# S7CAS-PLEIADES-CARTE-MERE_Pxx_CAN.net
KiCad netlist of a schematic drawn in Altium Designer
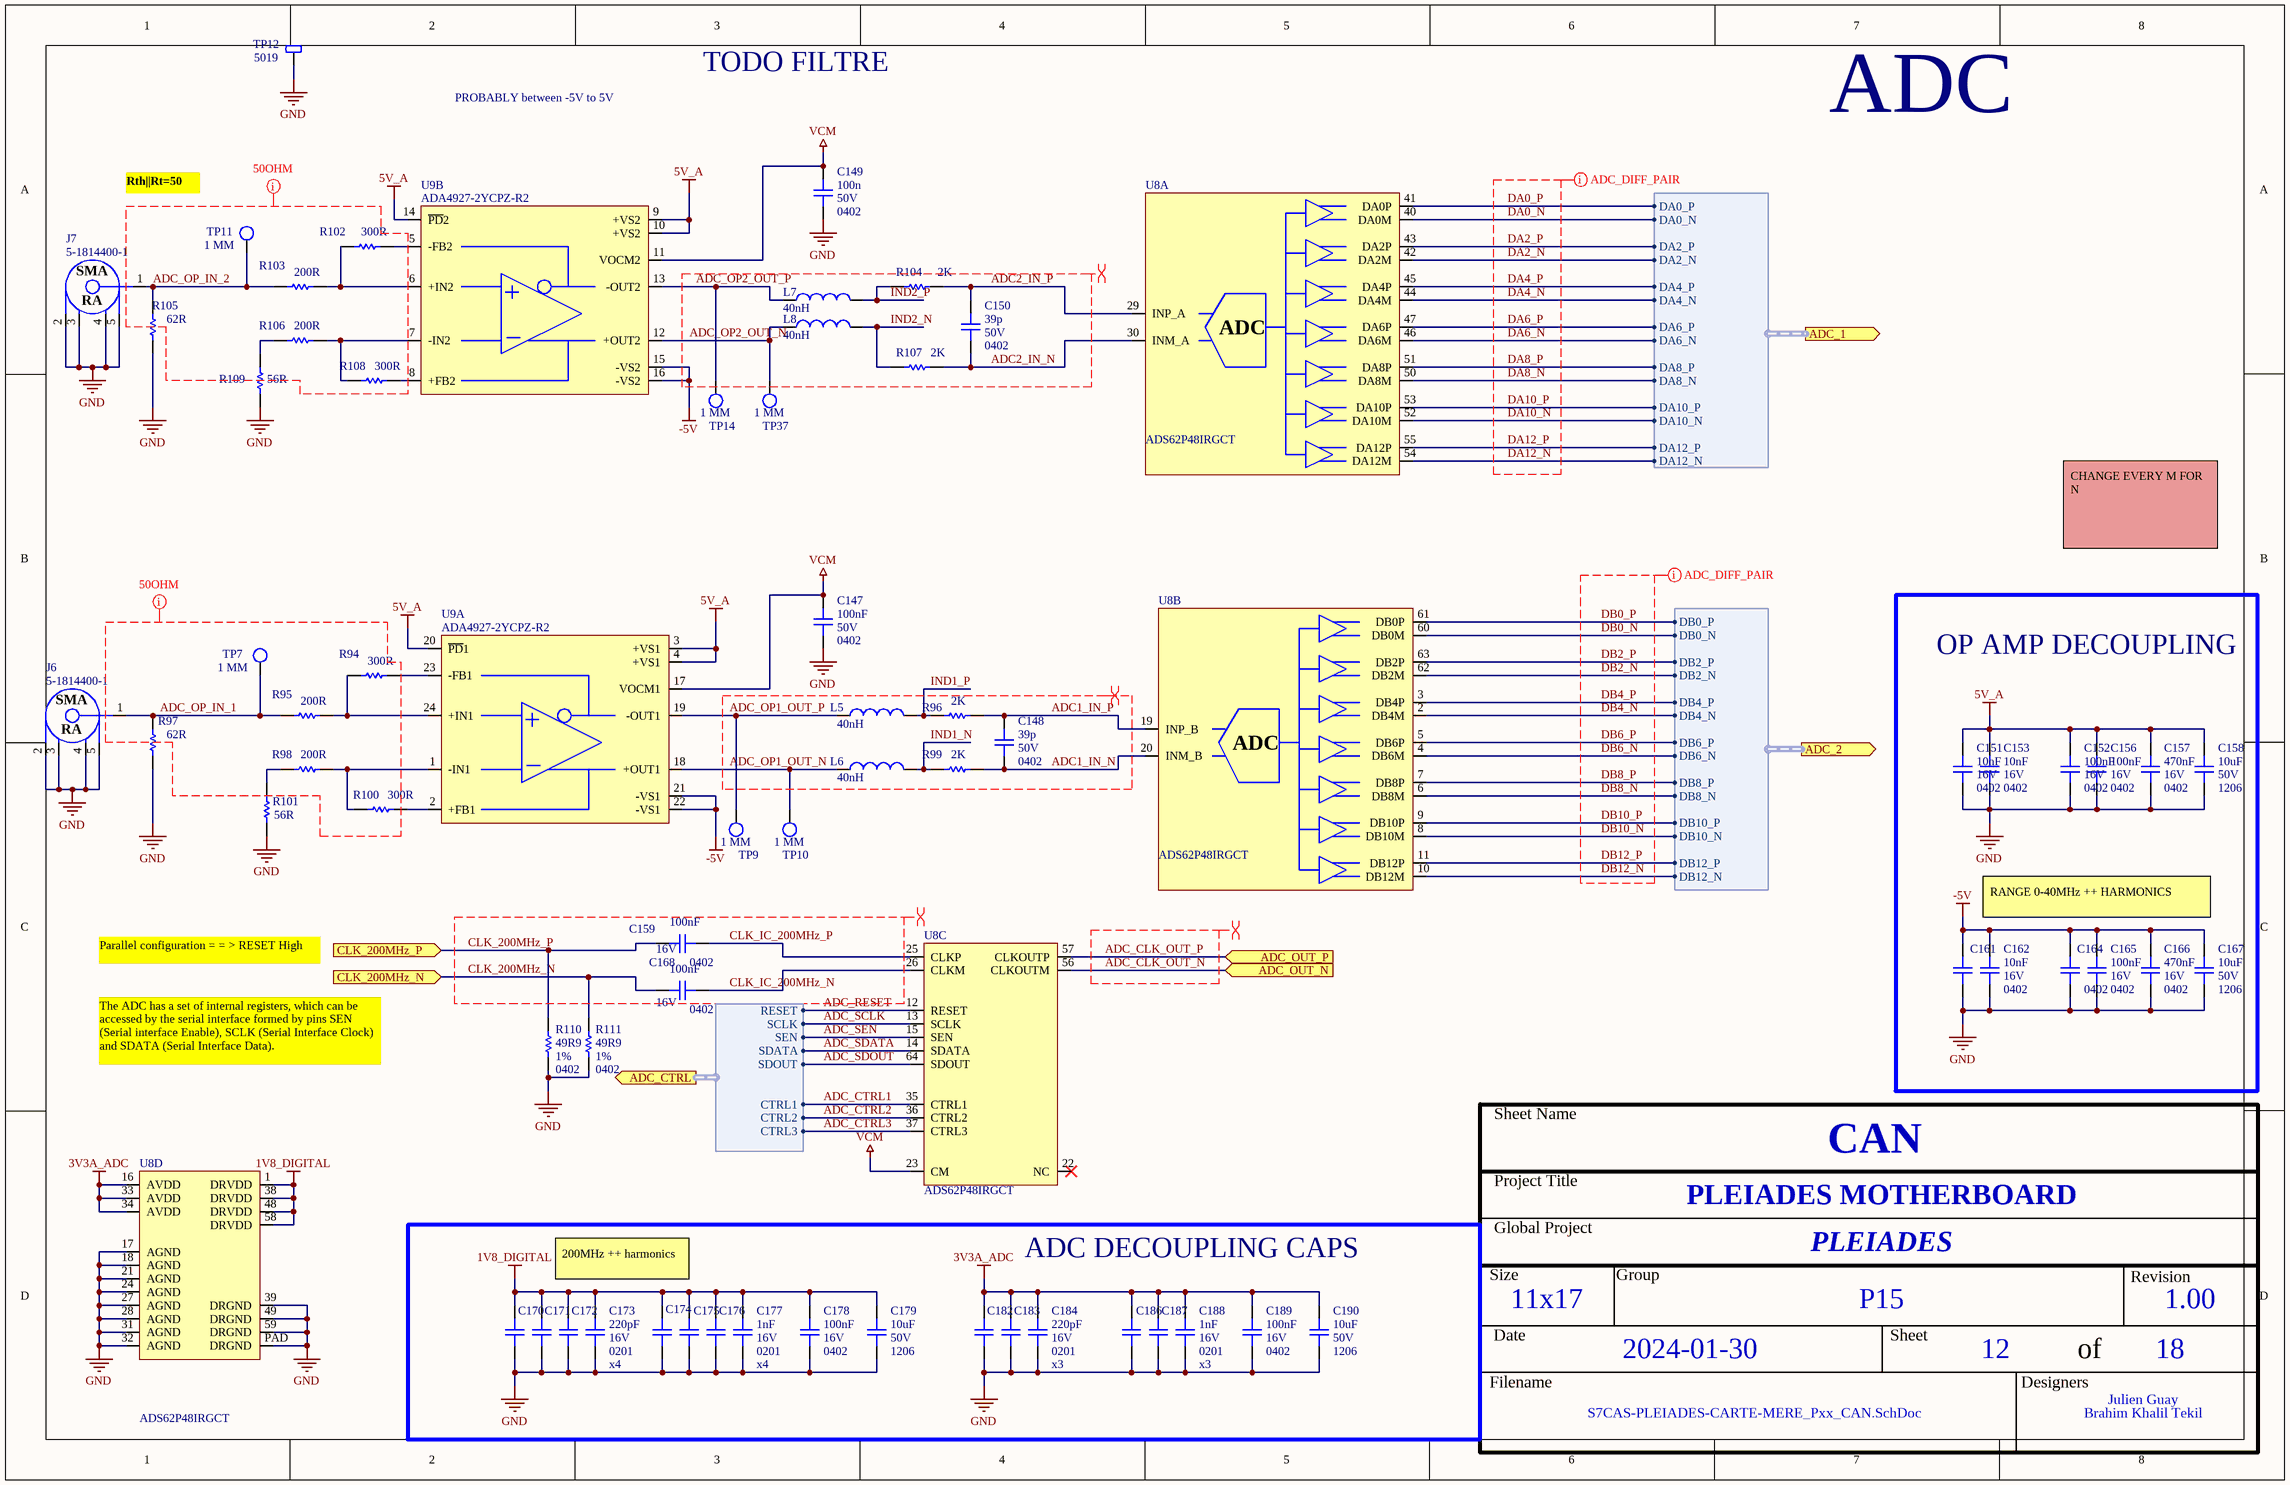
[diagram p0: S7CAS-PLEIADES-CARTE-MERE_Pxx_CAN.SchDoc]

(export (version "E")
  (design (tool "Eeschema 10.0.6"))
  (components
    (comp (ref "C147")
      (value "100nF")
      (footprint "S7CAS_LIB2023:CAP_0402")
      (description "CAP - 0402")
      (fields
        (field (name "VOLTAGE") "50V")
        (field (name "PACKAGE") "0402")
        (field (name "Comment") "0402")
        (field (name "CREATEDBY") "Jonathan Bouchard")
      )
      (libsource (lib "S7CAS_LIB2023") (part "CAP - 0603"))
    )
    (comp (ref "C148")
      (value "39p")
      (footprint "S7CAS_LIB2023:CAP_0402")
      (description "CAP - 0402")
      (fields
        (field (name "VOLTAGE") "50V")
        (field (name "PACKAGE") "0402")
        (field (name "Comment") "0402")
        (field (name "CREATEDBY") "Jonathan Bouchard")
      )
      (libsource (lib "S7CAS_LIB2023") (part "CAP - 0603"))
    )
    (comp (ref "C149")
      (value "100n")
      (footprint "S7CAS_LIB2023:CAP_0402")
      (description "CAP - 0402")
      (fields
        (field (name "VOLTAGE") "50V")
        (field (name "PACKAGE") "0402")
        (field (name "Comment") "0402")
        (field (name "CREATEDBY") "Jonathan Bouchard")
      )
      (libsource (lib "S7CAS_LIB2023") (part "CAP - 0603"))
    )
    (comp (ref "C150")
      (value "39p")
      (footprint "S7CAS_LIB2023:CAP_0402")
      (description "CAP - 0402")
      (fields
        (field (name "VOLTAGE") "50V")
        (field (name "PACKAGE") "0402")
        (field (name "Comment") "0402")
        (field (name "CREATEDBY") "Jonathan Bouchard")
      )
      (libsource (lib "S7CAS_LIB2023") (part "CAP - 0603"))
    )
    (comp (ref "C151")
      (value "10nF")
      (footprint "CAP_0402")
      (description "CAP - 0402")
      (fields
        (field (name "VOLTAGE") "16V")
        (field (name "PACKAGE") "0402")
        (field (name "CREATEDBY") "Jonathan Bouchard")
      )
      (libsource (lib "S7CAS_LIB2023") (part "CAP - 0402"))
    )
    (comp (ref "C152")
      (value "100nF")
      (footprint "S7CAS_LIB2023:CAP_0402")
      (description "CAP - 0402")
      (fields
        (field (name "VOLTAGE") "16V")
        (field (name "PACKAGE") "0402")
        (field (name "Comment") "0402")
        (field (name "CREATEDBY") "Jonathan Bouchard")
      )
      (libsource (lib "S7CAS_LIB2023") (part "CAP - 0603"))
    )
    (comp (ref "C153")
      (value "10nF")
      (footprint "CAP_0402")
      (description "CAP - 0402")
      (fields
        (field (name "VOLTAGE") "16V")
        (field (name "PACKAGE") "0402")
        (field (name "CREATEDBY") "Jonathan Bouchard")
      )
      (libsource (lib "S7CAS_LIB2023") (part "CAP - 0402"))
    )
    (comp (ref "C156")
      (value "100nF")
      (footprint "S7CAS_LIB2023:CAP_0402")
      (description "CAP - 0402")
      (fields
        (field (name "VOLTAGE") "16V")
        (field (name "PACKAGE") "0402")
        (field (name "Comment") "0402")
        (field (name "CREATEDBY") "Jonathan Bouchard")
      )
      (libsource (lib "S7CAS_LIB2023") (part "CAP - 0603"))
    )
    (comp (ref "C157")
      (value "470nF")
      (footprint "S7CAS_LIB2023:CAP_0402")
      (description "CAP - 0402")
      (fields
        (field (name "VOLTAGE") "16V")
        (field (name "PACKAGE") "0402")
        (field (name "Comment") "0402")
        (field (name "CREATEDBY") "Jonathan Bouchard")
      )
      (libsource (lib "S7CAS_LIB2023") (part "CAP - 0603"))
    )
    (comp (ref "C158")
      (value "10uF")
      (footprint "S7CAS_LIB2023:CAP_1206")
      (description "CAP - 1206")
      (fields
        (field (name "VOLTAGE") "50V")
        (field (name "PACKAGE") "1206")
        (field (name "CREATEDBY") "Jonathan Bouchard")
      )
      (libsource (lib "S7CAS_LIB2023") (part "CAP - 1206"))
    )
    (comp (ref "C159")
      (value "100nF")
      (footprint "S7CAS_LIB2023:CAP_0402")
      (description "CAP - 0402")
      (fields
        (field (name "VOLTAGE") "16V")
        (field (name "PACKAGE") "0402")
        (field (name "Comment") "0402")
        (field (name "CREATEDBY") "Jonathan Bouchard")
      )
      (libsource (lib "S7CAS_LIB2023") (part "CAP - 0603"))
    )
    (comp (ref "C161")
      (value "CAP - 0402")
      (footprint "CAP_0402")
      (fields (field (name "VOLTAGE") "16V") (field (name "CREATEDBY") "Jonathan Bouchard"))
      (libsource (lib "S7CAS_LIB2023") (part "CAP - 0402"))
    )
    (comp (ref "C162")
      (value "10nF")
      (footprint "CAP_0402")
      (description "CAP - 0402")
      (fields
        (field (name "VOLTAGE") "16V")
        (field (name "PACKAGE") "0402")
        (field (name "CREATEDBY") "Jonathan Bouchard")
      )
      (libsource (lib "S7CAS_LIB2023") (part "CAP - 0402"))
    )
    (comp (ref "C164")
      (value "0402")
      (footprint "S7CAS_LIB2023:CAP_0402")
      (description "CAP - 0402")
      (fields
        (field (name "VOLTAGE") "16V")
        (field (name "PACKAGE") "0402")
        (field (name "CREATEDBY") "Jonathan Bouchard")
      )
      (libsource (lib "S7CAS_LIB2023") (part "CAP - 0603"))
    )
    (comp (ref "C165")
      (value "100nF")
      (footprint "S7CAS_LIB2023:CAP_0402")
      (description "CAP - 0402")
      (fields
        (field (name "VOLTAGE") "16V")
        (field (name "PACKAGE") "0402")
        (field (name "Comment") "0402")
        (field (name "CREATEDBY") "Jonathan Bouchard")
      )
      (libsource (lib "S7CAS_LIB2023") (part "CAP - 0603"))
    )
    (comp (ref "C166")
      (value "470nF")
      (footprint "S7CAS_LIB2023:CAP_0402")
      (description "CAP - 0402")
      (fields
        (field (name "VOLTAGE") "16V")
        (field (name "PACKAGE") "0402")
        (field (name "Comment") "0402")
        (field (name "CREATEDBY") "Jonathan Bouchard")
      )
      (libsource (lib "S7CAS_LIB2023") (part "CAP - 0603"))
    )
    (comp (ref "C167")
      (value "10uF")
      (footprint "S7CAS_LIB2023:CAP_1206")
      (description "CAP - 1206")
      (fields
        (field (name "VOLTAGE") "50V")
        (field (name "PACKAGE") "1206")
        (field (name "CREATEDBY") "Jonathan Bouchard")
      )
      (libsource (lib "S7CAS_LIB2023") (part "CAP - 1206"))
    )
    (comp (ref "C168")
      (value "100nF")
      (footprint "S7CAS_LIB2023:CAP_0402")
      (description "CAP - 0402")
      (fields
        (field (name "VOLTAGE") "16V")
        (field (name "PACKAGE") "0402")
        (field (name "Comment") "0402")
        (field (name "CREATEDBY") "Jonathan Bouchard")
      )
      (libsource (lib "S7CAS_LIB2023") (part "CAP - 0603"))
    )
    (comp (ref "C170")
      (value "CAP - 0201")
      (footprint "CAP_0201")
      (fields (field (name "VOLTAGE") "16V") (field (name "CREATEDBY") "Jonathan Bouchard"))
      (libsource (lib "S7CAS_LIB2023") (part "CAP - 0201"))
    )
    (comp (ref "C171")
      (value "CAP - 0201")
      (footprint "CAP_0201")
      (fields (field (name "VOLTAGE") "16V") (field (name "CREATEDBY") "Jonathan Bouchard"))
      (libsource (lib "S7CAS_LIB2023") (part "CAP - 0201"))
    )
    (comp (ref "C172")
      (value "CAP - 0201")
      (footprint "CAP_0201")
      (fields (field (name "VOLTAGE") "16V") (field (name "CREATEDBY") "Jonathan Bouchard"))
      (libsource (lib "S7CAS_LIB2023") (part "CAP - 0201"))
    )
    (comp (ref "C173")
      (value "220pF")
      (footprint "CAP_0201")
      (description "CAP - 0201")
      (fields
        (field (name "VOLTAGE") "16V")
        (field (name "PACKAGE") "0201")
        (field (name "CREATEDBY") "Jonathan Bouchard")
      )
      (libsource (lib "S7CAS_LIB2023") (part "CAP - 0201"))
    )
    (comp (ref "C174")
      (value "CAP - 0201")
      (footprint "CAP_0201")
      (fields (field (name "VOLTAGE") "16V") (field (name "CREATEDBY") "Jonathan Bouchard"))
      (libsource (lib "S7CAS_LIB2023") (part "CAP - 0201"))
    )
    (comp (ref "C175")
      (value "CAP - 0201")
      (footprint "CAP_0201")
      (fields (field (name "VOLTAGE") "16V") (field (name "CREATEDBY") "Jonathan Bouchard"))
      (libsource (lib "S7CAS_LIB2023") (part "CAP - 0201"))
    )
    (comp (ref "C176")
      (value "CAP - 0201")
      (footprint "CAP_0201")
      (fields (field (name "VOLTAGE") "16V") (field (name "CREATEDBY") "Jonathan Bouchard"))
      (libsource (lib "S7CAS_LIB2023") (part "CAP - 0201"))
    )
    (comp (ref "C177")
      (value "1nF")
      (footprint "CAP_0201")
      (description "CAP - 0201")
      (fields
        (field (name "VOLTAGE") "16V")
        (field (name "PACKAGE") "0201")
        (field (name "CREATEDBY") "Jonathan Bouchard")
      )
      (libsource (lib "S7CAS_LIB2023") (part "CAP - 0201"))
    )
    (comp (ref "C178")
      (value "100nF")
      (footprint "S7CAS_LIB2023:CAP_0402")
      (description "CAP - 0402")
      (fields
        (field (name "VOLTAGE") "16V")
        (field (name "PACKAGE") "0402")
        (field (name "Comment") "0402")
        (field (name "CREATEDBY") "Jonathan Bouchard")
      )
      (libsource (lib "S7CAS_LIB2023") (part "CAP - 0603"))
    )
    (comp (ref "C179")
      (value "10uF")
      (footprint "S7CAS_LIB2023:CAP_1206")
      (description "CAP - 1206")
      (fields
        (field (name "VOLTAGE") "50V")
        (field (name "PACKAGE") "1206")
        (field (name "CREATEDBY") "Jonathan Bouchard")
      )
      (libsource (lib "S7CAS_LIB2023") (part "CAP - 1206"))
    )
    (comp (ref "C182")
      (value "CAP - 0201")
      (footprint "CAP_0201")
      (fields (field (name "VOLTAGE") "16V") (field (name "CREATEDBY") "Jonathan Bouchard"))
      (libsource (lib "S7CAS_LIB2023") (part "CAP - 0201"))
    )
    (comp (ref "C183")
      (value "CAP - 0201")
      (footprint "CAP_0201")
      (fields (field (name "VOLTAGE") "16V") (field (name "CREATEDBY") "Jonathan Bouchard"))
      (libsource (lib "S7CAS_LIB2023") (part "CAP - 0201"))
    )
    (comp (ref "C184")
      (value "220pF")
      (footprint "CAP_0201")
      (description "CAP - 0201")
      (fields
        (field (name "VOLTAGE") "16V")
        (field (name "PACKAGE") "0201")
        (field (name "CREATEDBY") "Jonathan Bouchard")
      )
      (libsource (lib "S7CAS_LIB2023") (part "CAP - 0201"))
    )
    (comp (ref "C186")
      (value "CAP - 0201")
      (footprint "CAP_0201")
      (fields (field (name "VOLTAGE") "16V") (field (name "CREATEDBY") "Jonathan Bouchard"))
      (libsource (lib "S7CAS_LIB2023") (part "CAP - 0201"))
    )
    (comp (ref "C187")
      (value "CAP - 0201")
      (footprint "CAP_0201")
      (fields (field (name "VOLTAGE") "16V") (field (name "CREATEDBY") "Jonathan Bouchard"))
      (libsource (lib "S7CAS_LIB2023") (part "CAP - 0201"))
    )
    (comp (ref "C188")
      (value "1nF")
      (footprint "CAP_0201")
      (description "CAP - 0201")
      (fields
        (field (name "VOLTAGE") "16V")
        (field (name "PACKAGE") "0201")
        (field (name "CREATEDBY") "Jonathan Bouchard")
      )
      (libsource (lib "S7CAS_LIB2023") (part "CAP - 0201"))
    )
    (comp (ref "C189")
      (value "100nF")
      (footprint "S7CAS_LIB2023:CAP_0402")
      (description "CAP - 0402")
      (fields
        (field (name "VOLTAGE") "16V")
        (field (name "PACKAGE") "0402")
        (field (name "Comment") "0402")
        (field (name "CREATEDBY") "Jonathan Bouchard")
      )
      (libsource (lib "S7CAS_LIB2023") (part "CAP - 0603"))
    )
    (comp (ref "C190")
      (value "10uF")
      (footprint "S7CAS_LIB2023:CAP_1206")
      (description "CAP - 1206")
      (fields
        (field (name "VOLTAGE") "50V")
        (field (name "PACKAGE") "1206")
        (field (name "CREATEDBY") "Jonathan Bouchard")
      )
      (libsource (lib "S7CAS_LIB2023") (part "CAP - 1206"))
    )
    (comp (ref "J6")
      (value "5-1814400-1")
      (footprint "CONN_SMA_5-1814400-1")
      (description "CONN -  SMA JACK R/A 50 OHM - TH")
      (fields
        (field (name "MFG") "TE Connectivity AMP Connectors")
        (field (name "CREATEDBY") "Jonathan Bouchard")
      )
      (libsource (lib "S7CAS_LIB2023") (part "CONN_SMA_5-1814400-1"))
    )
    (comp (ref "J7")
      (value "5-1814400-1")
      (footprint "CONN_SMA_5-1814400-1")
      (description "CONN -  SMA JACK R/A 50 OHM - TH")
      (fields
        (field (name "MFG") "TE Connectivity AMP Connectors")
        (field (name "CREATEDBY") "Jonathan Bouchard")
      )
      (libsource (lib "S7CAS_LIB2023") (part "CONN_SMA_5-1814400-1"))
    )
    (comp (ref "L5")
      (value "40nH")
      (footprint "S7CAS_LIB2023:IND - 0402")
      (description "INDUCTOR - 0402")
      (libsource (lib "S7CAS_LIB2023") (part "INDUCT - 0402"))
    )
    (comp (ref "L6")
      (value "40nH")
      (footprint "S7CAS_LIB2023:IND - 0402")
      (description "INDUCTOR - 0402")
      (libsource (lib "S7CAS_LIB2023") (part "INDUCT - 0402"))
    )
    (comp (ref "L7")
      (value "40nH")
      (footprint "S7CAS_LIB2023:IND - 0402")
      (description "INDUCTOR - 0402")
      (libsource (lib "S7CAS_LIB2023") (part "INDUCT - 0402"))
    )
    (comp (ref "L8")
      (value "40nH")
      (footprint "S7CAS_LIB2023:IND - 0402")
      (description "INDUCTOR - 0402")
      (libsource (lib "S7CAS_LIB2023") (part "INDUCT - 0402"))
    )
    (comp (ref "R94")
      (value "300R")
      (footprint "S7CAS_LIB2023:RES_0402")
      (description "RES - 0402")
      (fields (field (name "Comment") "RES - 0603") (field (name "CREATEDBY") "Jonathan Bouchard"))
      (libsource (lib "S7CAS_LIB2023") (part "RES - 0603"))
    )
    (comp (ref "R95")
      (value "200R")
      (footprint "S7CAS_LIB2023:RES_0402")
      (description "RES - 0402")
      (fields (field (name "Comment") "RES - 0603") (field (name "CREATEDBY") "Jonathan Bouchard"))
      (libsource (lib "S7CAS_LIB2023") (part "RES - 0603"))
    )
    (comp (ref "R96")
      (value "2K")
      (footprint "S7CAS_LIB2023:RES_0402")
      (description "RES - 0402")
      (fields (field (name "Comment") "RES - 0603") (field (name "CREATEDBY") "Jonathan Bouchard"))
      (libsource (lib "S7CAS_LIB2023") (part "RES - 0603"))
    )
    (comp (ref "R97")
      (value "62R")
      (footprint "S7CAS_LIB2023:RES_0402")
      (description "RES - 0402")
      (fields (field (name "Comment") "RES - 0603") (field (name "CREATEDBY") "Jonathan Bouchard"))
      (libsource (lib "S7CAS_LIB2023") (part "RES - 0603"))
    )
    (comp (ref "R98")
      (value "200R")
      (footprint "S7CAS_LIB2023:RES_0402")
      (description "RES - 0402")
      (fields (field (name "Comment") "RES - 0603") (field (name "CREATEDBY") "Jonathan Bouchard"))
      (libsource (lib "S7CAS_LIB2023") (part "RES - 0603"))
    )
    (comp (ref "R99")
      (value "2K")
      (footprint "S7CAS_LIB2023:RES_0402")
      (description "RES - 0402")
      (fields (field (name "Comment") "RES - 0603") (field (name "CREATEDBY") "Jonathan Bouchard"))
      (libsource (lib "S7CAS_LIB2023") (part "RES - 0603"))
    )
    (comp (ref "R100")
      (value "300R")
      (footprint "S7CAS_LIB2023:RES_0402")
      (description "RES - 0402")
      (fields (field (name "Comment") "RES - 0603") (field (name "CREATEDBY") "Jonathan Bouchard"))
      (libsource (lib "S7CAS_LIB2023") (part "RES - 0603"))
    )
    (comp (ref "R101")
      (value "56R")
      (footprint "S7CAS_LIB2023:RES_0402")
      (description "RES - 0402")
      (fields (field (name "Comment") "RES - 0603") (field (name "CREATEDBY") "Jonathan Bouchard"))
      (libsource (lib "S7CAS_LIB2023") (part "RES - 0603"))
    )
    (comp (ref "R102")
      (value "300R")
      (footprint "S7CAS_LIB2023:RES_0402")
      (description "RES - 0402")
      (fields (field (name "Comment") "RES - 0603") (field (name "CREATEDBY") "Jonathan Bouchard"))
      (libsource (lib "S7CAS_LIB2023") (part "RES - 0603"))
    )
    (comp (ref "R103")
      (value "200R")
      (footprint "S7CAS_LIB2023:RES_0402")
      (description "RES - 0402")
      (fields (field (name "Comment") "RES - 0603") (field (name "CREATEDBY") "Jonathan Bouchard"))
      (libsource (lib "S7CAS_LIB2023") (part "RES - 0603"))
    )
    (comp (ref "R104")
      (value "2K")
      (footprint "S7CAS_LIB2023:RES_0402")
      (description "RES - 0402")
      (fields (field (name "Comment") "RES - 0603") (field (name "CREATEDBY") "Jonathan Bouchard"))
      (libsource (lib "S7CAS_LIB2023") (part "RES - 0603"))
    )
    (comp (ref "R105")
      (value "62R")
      (footprint "S7CAS_LIB2023:RES_0402")
      (description "RES - 0402")
      (fields (field (name "Comment") "RES - 0603") (field (name "CREATEDBY") "Jonathan Bouchard"))
      (libsource (lib "S7CAS_LIB2023") (part "RES - 0603"))
    )
    (comp (ref "R106")
      (value "200R")
      (footprint "S7CAS_LIB2023:RES_0402")
      (description "RES - 0402")
      (fields (field (name "Comment") "RES - 0603") (field (name "CREATEDBY") "Jonathan Bouchard"))
      (libsource (lib "S7CAS_LIB2023") (part "RES - 0603"))
    )
    (comp (ref "R107")
      (value "2K")
      (footprint "S7CAS_LIB2023:RES_0402")
      (description "RES - 0402")
      (fields (field (name "Comment") "RES - 0603") (field (name "CREATEDBY") "Jonathan Bouchard"))
      (libsource (lib "S7CAS_LIB2023") (part "RES - 0603"))
    )
    (comp (ref "R108")
      (value "300R")
      (footprint "S7CAS_LIB2023:RES_0402")
      (description "RES - 0402")
      (fields (field (name "Comment") "RES - 0603") (field (name "CREATEDBY") "Jonathan Bouchard"))
      (libsource (lib "S7CAS_LIB2023") (part "RES - 0603"))
    )
    (comp (ref "R109")
      (value "56R")
      (footprint "S7CAS_LIB2023:RES_0402")
      (description "RES - 0402")
      (fields (field (name "Comment") "RES - 0603") (field (name "CREATEDBY") "Jonathan Bouchard"))
      (libsource (lib "S7CAS_LIB2023") (part "RES - 0603"))
    )
    (comp (ref "R110")
      (value "49R9")
      (footprint "S7CAS_LIB2023:RES_0402")
      (description "RES - 0402")
      (fields
        (field (name "PACKAGE") "0402")
        (field (name "PRECISION") "1%")
        (field (name "Comment") "RES - 0603")
        (field (name "CREATEDBY") "Jonathan Bouchard")
      )
      (libsource (lib "S7CAS_LIB2023") (part "RES - 0603"))
    )
    (comp (ref "R111")
      (value "49R9")
      (footprint "S7CAS_LIB2023:RES_0402")
      (description "RES - 0402")
      (fields
        (field (name "PACKAGE") "0402")
        (field (name "PRECISION") "1%")
        (field (name "Comment") "RES - 0603")
        (field (name "CREATEDBY") "Jonathan Bouchard")
      )
      (libsource (lib "S7CAS_LIB2023") (part "RES - 0603"))
    )
    (comp (ref "TP7")
      (value "1 MM")
      (footprint "TPO_SMD_ROUND_1MM")
      (description "TPO - TEST POINT ROUND SMD PAD ONLY  - 1 MM")
      (fields
        (field (name "CREATEDBY/DATE") "Jonathan Bouchard 2018-07-17")
        (field (name "VERIFIEDBY") "Arnaud Samson 23-07-18")
      )
      (libsource (lib "S7CAS_LIB2023") (part "TPO_SMD_ROUND_1MM"))
    )
    (comp (ref "TP9")
      (value "1 MM")
      (footprint "TPO_SMD_ROUND_1MM")
      (description "TPO - TEST POINT ROUND SMD PAD ONLY  - 1 MM")
      (fields
        (field (name "CREATEDBY/DATE") "Jonathan Bouchard 2018-07-17")
        (field (name "VERIFIEDBY") "Arnaud Samson 23-07-18")
      )
      (libsource (lib "S7CAS_LIB2023") (part "TPO_SMD_ROUND_1MM"))
    )
    (comp (ref "TP10")
      (value "1 MM")
      (footprint "TPO_SMD_ROUND_1MM")
      (description "TPO - TEST POINT ROUND SMD PAD ONLY  - 1 MM")
      (fields
        (field (name "CREATEDBY/DATE") "Jonathan Bouchard 2018-07-17")
        (field (name "VERIFIEDBY") "Arnaud Samson 23-07-18")
      )
      (libsource (lib "S7CAS_LIB2023") (part "TPO_SMD_ROUND_1MM"))
    )
    (comp (ref "TP11")
      (value "1 MM")
      (footprint "TPO_SMD_ROUND_1MM")
      (description "TPO - TEST POINT ROUND SMD PAD ONLY  - 1 MM")
      (fields
        (field (name "CREATEDBY/DATE") "Jonathan Bouchard 2018-07-17")
        (field (name "VERIFIEDBY") "Arnaud Samson 23-07-18")
      )
      (libsource (lib "S7CAS_LIB2023") (part "TPO_SMD_ROUND_1MM"))
    )
    (comp (ref "TP12")
      (value "5019")
      (footprint "TPO_SMD_5019")
      (description "TPO - PC TEST POINT MINI - SMD")
      (fields
        (field (name "CREATEDBY/DATE") "Olivier Bernard / 5/12/2017")
        (field (name "VERIFIEDBY") "Caroline Paulin / 5 juillet 2018")
      )
      (libsource (lib "S7CAS_LIB2023") (part "TPO_SMD_5019"))
    )
    (comp (ref "TP14")
      (value "1 MM")
      (footprint "TPO_SMD_ROUND_1MM")
      (description "TPO - TEST POINT ROUND SMD PAD ONLY  - 1 MM")
      (fields
        (field (name "CREATEDBY/DATE") "Jonathan Bouchard 2018-07-17")
        (field (name "VERIFIEDBY") "Arnaud Samson 23-07-18")
      )
      (libsource (lib "S7CAS_LIB2023") (part "TPO_SMD_ROUND_1MM"))
    )
    (comp (ref "TP37")
      (value "1 MM")
      (footprint "TPO_SMD_ROUND_1MM")
      (description "TPO - TEST POINT ROUND SMD PAD ONLY  - 1 MM")
      (fields
        (field (name "CREATEDBY/DATE") "Jonathan Bouchard 2018-07-17")
        (field (name "VERIFIEDBY") "Arnaud Samson 23-07-18")
      )
      (libsource (lib "S7CAS_LIB2023") (part "TPO_SMD_ROUND_1MM"))
    )
    (comp (ref "U8")
      (value "ADS62P48IRGCT")
      (footprint "ADC_ADS62P48IRGCT")
      (description "ADC - 14 BIT 210MSPS SUAL - VQFN-64")
      (fields
        (field (name "VOLTAGE") "3.15 V ~ 3.6 V / 1.7 V ~ 1.9 V")
        (field (name "MFG") "Texas Instruments")
        (field (name "CREATEDBY") "Jonathan Bouchard")
      )
      (libsource (lib "S7CAS_LIB2023") (part "ADC_ADS62P48IRGCT"))
    )
    (comp (ref "U9")
      (value "ADA4927-2YCPZ-R2")
      (footprint "OPAMP_ADA4927-2YCPZ-R2")
      (description "OPAMP - CFA 2.3GHZ - QFN-24")
      (fields
        (field (name "VOLTAGE") "4.5 V ~ 11 V, ±2.25 V ~ 5.5 V")
        (field (name "MFG") "Analog Devices")
        (field (name "CREATEDBY") "Jonathan Bouchard")
      )
      (libsource (lib "S7CAS_LIB2023") (part "OPAMP_ADA4927-2YCPZ-R2"))
    )
  )
  (nets
    (net (code "4") (name "-5V") (class "Default")
      (node (ref "C161") (pin "2") (pinfunction "2_2") (pintype "passive"))
      (node (ref "C162") (pin "2") (pinfunction "2_2") (pintype "passive"))
      (node (ref "C164") (pin "2") (pinfunction "2_2") (pintype "passive"))
      (node (ref "C165") (pin "2") (pinfunction "2_2") (pintype "passive"))
      (node (ref "C166") (pin "2") (pinfunction "2_2") (pintype "passive"))
      (node (ref "C167") (pin "2") (pinfunction "2_2") (pintype "passive"))
      (node (ref "U9") (pin "15") (pinfunction "-VS2_15") (pintype "passive"))
      (node (ref "U9") (pin "16") (pinfunction "-VS2_16") (pintype "passive"))
      (node (ref "U9") (pin "21") (pinfunction "-VS1_21") (pintype "passive"))
      (node (ref "U9") (pin "22") (pinfunction "-VS1_22") (pintype "passive"))
    )
    (net (code "5") (name "/ADC1_IN_N") (class "Default")
      (node (ref "C148") (pin "1") (pinfunction "1_1") (pintype "passive"))
      (node (ref "R99") (pin "1") (pinfunction "1_1") (pintype "passive"))
      (node (ref "U8") (pin "20") (pinfunction "INM_B_20") (pintype "passive"))
    )
    (net (code "6") (name "/ADC1_IN_P") (class "Default")
      (node (ref "C148") (pin "2") (pinfunction "2_2") (pintype "passive"))
      (node (ref "R96") (pin "1") (pinfunction "1_1") (pintype "passive"))
      (node (ref "U8") (pin "19") (pinfunction "INP_B_19") (pintype "passive"))
    )
    (net (code "7") (name "/ADC2_IN_N") (class "Default")
      (node (ref "C150") (pin "1") (pinfunction "1_1") (pintype "passive"))
      (node (ref "R107") (pin "1") (pinfunction "1_1") (pintype "passive"))
      (node (ref "U8") (pin "30") (pinfunction "INM_A_30") (pintype "passive"))
    )
    (net (code "8") (name "/ADC2_IN_P") (class "Default")
      (node (ref "C150") (pin "2") (pinfunction "2_2") (pintype "passive"))
      (node (ref "R104") (pin "1") (pinfunction "1_1") (pintype "passive"))
      (node (ref "U8") (pin "29") (pinfunction "INP_A_29") (pintype "passive"))
    )
    (net (code "9") (name "/ADC_CLK_OUT_N") (class "Default")
      (node (ref "U8") (pin "56") (pinfunction "CLKOUTM_56") (pintype "passive"))
    )
    (net (code "10") (name "/ADC_CLK_OUT_P") (class "Default")
      (node (ref "U8") (pin "57") (pinfunction "CLKOUTP_57") (pintype "passive"))
    )
    (net (code "11") (name "/ADC_CTRL1") (class "Default")
      (node (ref "U8") (pin "35") (pinfunction "CTRL1_35") (pintype "passive"))
    )
    (net (code "12") (name "/ADC_CTRL2") (class "Default")
      (node (ref "U8") (pin "36") (pinfunction "CTRL2_36") (pintype "passive"))
    )
    (net (code "13") (name "/ADC_CTRL3") (class "Default")
      (node (ref "U8") (pin "37") (pinfunction "CTRL3_37") (pintype "passive"))
    )
    (net (code "14") (name "/ADC_OP1_OUT_N") (class "Default")
      (node (ref "L6") (pin "1") (pinfunction "1_1") (pintype "passive"))
      (node (ref "TP10") (pin "1") (pinfunction "1_1") (pintype "passive"))
      (node (ref "U9") (pin "18") (pinfunction "+OUT1_18") (pintype "passive"))
    )
    (net (code "15") (name "/ADC_OP1_OUT_P") (class "Default")
      (node (ref "L5") (pin "1") (pinfunction "1_1") (pintype "passive"))
      (node (ref "TP9") (pin "1") (pinfunction "1_1") (pintype "passive"))
      (node (ref "U9") (pin "19") (pinfunction "-OUT1_19") (pintype "passive"))
    )
    (net (code "16") (name "/ADC_OP2_OUT_N") (class "Default")
      (node (ref "L8") (pin "1") (pinfunction "1_1") (pintype "passive"))
      (node (ref "TP37") (pin "1") (pinfunction "1_1") (pintype "passive"))
      (node (ref "U9") (pin "12") (pinfunction "+OUT2_12") (pintype "passive"))
    )
    (net (code "17") (name "/ADC_OP2_OUT_P") (class "Default")
      (node (ref "L7") (pin "1") (pinfunction "1_1") (pintype "passive"))
      (node (ref "TP14") (pin "1") (pinfunction "1_1") (pintype "passive"))
      (node (ref "U9") (pin "13") (pinfunction "-OUT2_13") (pintype "passive"))
    )
    (net (code "18") (name "/ADC_OP_IN_1") (class "Default")
      (node (ref "J6") (pin "1") (pinfunction "1_1") (pintype "passive"))
      (node (ref "R95") (pin "2") (pinfunction "2_2") (pintype "passive"))
      (node (ref "R97") (pin "2") (pinfunction "2_2") (pintype "passive"))
      (node (ref "TP7") (pin "1") (pinfunction "1_1") (pintype "passive"))
    )
    (net (code "19") (name "/ADC_OP_IN_2") (class "Default")
      (node (ref "J7") (pin "1") (pinfunction "1_1") (pintype "passive"))
      (node (ref "R103") (pin "2") (pinfunction "2_2") (pintype "passive"))
      (node (ref "R105") (pin "2") (pinfunction "2_2") (pintype "passive"))
      (node (ref "TP11") (pin "1") (pinfunction "1_1") (pintype "passive"))
    )
    (net (code "20") (name "/ADC_RESET") (class "Default")
      (node (ref "U8") (pin "12") (pinfunction "RESET_12") (pintype "passive"))
    )
    (net (code "21") (name "/ADC_SCLK") (class "Default")
      (node (ref "U8") (pin "13") (pinfunction "SCLK_13") (pintype "passive"))
    )
    (net (code "22") (name "/ADC_SDATA") (class "Default")
      (node (ref "U8") (pin "14") (pinfunction "SDATA_14") (pintype "passive"))
    )
    (net (code "23") (name "/ADC_SDOUT") (class "Default")
      (node (ref "U8") (pin "64") (pinfunction "SDOUT_64") (pintype "passive"))
    )
    (net (code "24") (name "/ADC_SEN") (class "Default")
      (node (ref "U8") (pin "15") (pinfunction "SEN_15") (pintype "passive"))
    )
    (net (code "25") (name "/CLK_200MHz_N") (class "Default")
      (node (ref "C168") (pin "2") (pinfunction "2_2") (pintype "passive"))
      (node (ref "R111") (pin "2") (pinfunction "2_2") (pintype "passive"))
    )
    (net (code "26") (name "/CLK_200MHz_P") (class "Default")
      (node (ref "C159") (pin "2") (pinfunction "2_2") (pintype "passive"))
      (node (ref "R110") (pin "2") (pinfunction "2_2") (pintype "passive"))
    )
    (net (code "27") (name "/CLK_IC_200MHz_N") (class "Default")
      (node (ref "C168") (pin "1") (pinfunction "1_1") (pintype "passive"))
      (node (ref "U8") (pin "26") (pinfunction "CLKM_26") (pintype "passive"))
    )
    (net (code "28") (name "/CLK_IC_200MHz_P") (class "Default")
      (node (ref "C159") (pin "1") (pinfunction "1_1") (pintype "passive"))
      (node (ref "U8") (pin "25") (pinfunction "CLKP_25") (pintype "passive"))
    )
    (net (code "29") (name "/DA0_N") (class "Default")
      (node (ref "U8") (pin "40") (pinfunction "DA0M_40") (pintype "passive"))
    )
    (net (code "30") (name "/DA0_P") (class "Default")
      (node (ref "U8") (pin "41") (pinfunction "DA0P_41") (pintype "passive"))
    )
    (net (code "31") (name "/DA2_N") (class "Default")
      (node (ref "U8") (pin "42") (pinfunction "DA2M_42") (pintype "passive"))
    )
    (net (code "32") (name "/DA2_P") (class "Default")
      (node (ref "U8") (pin "43") (pinfunction "DA2P_43") (pintype "passive"))
    )
    (net (code "33") (name "/DA4_N") (class "Default")
      (node (ref "U8") (pin "44") (pinfunction "DA4M_44") (pintype "passive"))
    )
    (net (code "34") (name "/DA4_P") (class "Default")
      (node (ref "U8") (pin "45") (pinfunction "DA4P_45") (pintype "passive"))
    )
    (net (code "35") (name "/DA6_N") (class "Default")
      (node (ref "U8") (pin "46") (pinfunction "DA6M_46") (pintype "passive"))
    )
    (net (code "36") (name "/DA6_P") (class "Default")
      (node (ref "U8") (pin "47") (pinfunction "DA6P_47") (pintype "passive"))
    )
    (net (code "37") (name "/DA8_N") (class "Default")
      (node (ref "U8") (pin "50") (pinfunction "DA8M_50") (pintype "passive"))
    )
    (net (code "38") (name "/DA8_P") (class "Default")
      (node (ref "U8") (pin "51") (pinfunction "DA8P_51") (pintype "passive"))
    )
    (net (code "39") (name "/DA10_N") (class "Default")
      (node (ref "U8") (pin "52") (pinfunction "DA10M_52") (pintype "passive"))
    )
    (net (code "40") (name "/DA10_P") (class "Default")
      (node (ref "U8") (pin "53") (pinfunction "DA10P_53") (pintype "passive"))
    )
    (net (code "41") (name "/DA12_N") (class "Default")
      (node (ref "U8") (pin "54") (pinfunction "DA12M_54") (pintype "passive"))
    )
    (net (code "42") (name "/DA12_P") (class "Default")
      (node (ref "U8") (pin "55") (pinfunction "DA12P_55") (pintype "passive"))
    )
    (net (code "43") (name "/DB0_N") (class "Default")
      (node (ref "U8") (pin "60") (pinfunction "DB0M_60") (pintype "passive"))
    )
    (net (code "44") (name "/DB0_P") (class "Default")
      (node (ref "U8") (pin "61") (pinfunction "DB0P_61") (pintype "passive"))
    )
    (net (code "45") (name "/DB2_N") (class "Default")
      (node (ref "U8") (pin "62") (pinfunction "DB2M_62") (pintype "passive"))
    )
    (net (code "46") (name "/DB2_P") (class "Default")
      (node (ref "U8") (pin "63") (pinfunction "DB2P_63") (pintype "passive"))
    )
    (net (code "47") (name "/DB4_N") (class "Default")
      (node (ref "U8") (pin "2") (pinfunction "DB4M_2") (pintype "passive"))
    )
    (net (code "48") (name "/DB4_P") (class "Default")
      (node (ref "U8") (pin "3") (pinfunction "DB4P_3") (pintype "passive"))
    )
    (net (code "49") (name "/DB6_N") (class "Default")
      (node (ref "U8") (pin "4") (pinfunction "DB6M_4") (pintype "passive"))
    )
    (net (code "50") (name "/DB6_P") (class "Default")
      (node (ref "U8") (pin "5") (pinfunction "DB6P_5") (pintype "passive"))
    )
    (net (code "51") (name "/DB8_N") (class "Default")
      (node (ref "U8") (pin "6") (pinfunction "DB8M_6") (pintype "passive"))
    )
    (net (code "52") (name "/DB8_P") (class "Default")
      (node (ref "U8") (pin "7") (pinfunction "DB8P_7") (pintype "passive"))
    )
    (net (code "53") (name "/DB10_N") (class "Default")
      (node (ref "U8") (pin "8") (pinfunction "DB10M_8") (pintype "passive"))
    )
    (net (code "54") (name "/DB10_P") (class "Default")
      (node (ref "U8") (pin "9") (pinfunction "DB10P_9") (pintype "passive"))
    )
    (net (code "55") (name "/DB12_N") (class "Default")
      (node (ref "U8") (pin "10") (pinfunction "DB12M_10") (pintype "passive"))
    )
    (net (code "56") (name "/DB12_P") (class "Default")
      (node (ref "U8") (pin "11") (pinfunction "DB12P_11") (pintype "passive"))
    )
    (net (code "57") (name "/IND1_N") (class "Default")
      (node (ref "L6") (pin "2") (pinfunction "2_2") (pintype "passive"))
      (node (ref "R99") (pin "2") (pinfunction "2_2") (pintype "passive"))
    )
    (net (code "58") (name "/IND1_P") (class "Default")
      (node (ref "L5") (pin "2") (pinfunction "2_2") (pintype "passive"))
      (node (ref "R96") (pin "2") (pinfunction "2_2") (pintype "passive"))
    )
    (net (code "59") (name "/IND2_N") (class "Default")
      (node (ref "L8") (pin "2") (pinfunction "2_2") (pintype "passive"))
      (node (ref "R107") (pin "2") (pinfunction "2_2") (pintype "passive"))
    )
    (net (code "60") (name "/IND2_P") (class "Default")
      (node (ref "L7") (pin "2") (pinfunction "2_2") (pintype "passive"))
      (node (ref "R104") (pin "2") (pinfunction "2_2") (pintype "passive"))
    )
    (net (code "64") (name "1V8_DIGITAL") (class "Default")
      (node (ref "C170") (pin "2") (pinfunction "2_2") (pintype "passive"))
      (node (ref "C171") (pin "2") (pinfunction "2_2") (pintype "passive"))
      (node (ref "C172") (pin "2") (pinfunction "2_2") (pintype "passive"))
      (node (ref "C173") (pin "2") (pinfunction "2_2") (pintype "passive"))
      (node (ref "C174") (pin "2") (pinfunction "2_2") (pintype "passive"))
      (node (ref "C175") (pin "2") (pinfunction "2_2") (pintype "passive"))
      (node (ref "C176") (pin "2") (pinfunction "2_2") (pintype "passive"))
      (node (ref "C177") (pin "2") (pinfunction "2_2") (pintype "passive"))
      (node (ref "C178") (pin "2") (pinfunction "2_2") (pintype "passive"))
      (node (ref "C179") (pin "2") (pinfunction "2_2") (pintype "passive"))
      (node (ref "U8") (pin "1") (pinfunction "DRVDD_1") (pintype "passive"))
      (node (ref "U8") (pin "38") (pinfunction "DRVDD_38") (pintype "passive"))
      (node (ref "U8") (pin "48") (pinfunction "DRVDD_48") (pintype "passive"))
      (node (ref "U8") (pin "58") (pinfunction "DRVDD_58") (pintype "passive"))
    )
    (net (code "65") (name "3V3A_ADC") (class "Default")
      (node (ref "C182") (pin "2") (pinfunction "2_2") (pintype "passive"))
      (node (ref "C183") (pin "2") (pinfunction "2_2") (pintype "passive"))
      (node (ref "C184") (pin "2") (pinfunction "2_2") (pintype "passive"))
      (node (ref "C186") (pin "2") (pinfunction "2_2") (pintype "passive"))
      (node (ref "C187") (pin "2") (pinfunction "2_2") (pintype "passive"))
      (node (ref "C188") (pin "2") (pinfunction "2_2") (pintype "passive"))
      (node (ref "C189") (pin "2") (pinfunction "2_2") (pintype "passive"))
      (node (ref "C190") (pin "2") (pinfunction "2_2") (pintype "passive"))
      (node (ref "U8") (pin "16") (pinfunction "AVDD_16") (pintype "passive"))
      (node (ref "U8") (pin "33") (pinfunction "AVDD_33") (pintype "passive"))
      (node (ref "U8") (pin "34") (pinfunction "AVDD_34") (pintype "passive"))
    )
    (net (code "66") (name "5V_A") (class "Default")
      (node (ref "C151") (pin "2") (pinfunction "2_2") (pintype "passive"))
      (node (ref "C152") (pin "2") (pinfunction "2_2") (pintype "passive"))
      (node (ref "C153") (pin "2") (pinfunction "2_2") (pintype "passive"))
      (node (ref "C156") (pin "2") (pinfunction "2_2") (pintype "passive"))
      (node (ref "C157") (pin "2") (pinfunction "2_2") (pintype "passive"))
      (node (ref "C158") (pin "2") (pinfunction "2_2") (pintype "passive"))
      (node (ref "U9") (pin "10") (pinfunction "+VS2_10") (pintype "passive"))
      (node (ref "U9") (pin "14") (pinfunction "~{PD}2_14") (pintype "passive"))
      (node (ref "U9") (pin "20") (pinfunction "~{PD}1_20") (pintype "passive"))
      (node (ref "U9") (pin "3") (pinfunction "+VS1_3") (pintype "passive"))
      (node (ref "U9") (pin "4") (pinfunction "+VS1_4") (pintype "passive"))
      (node (ref "U9") (pin "9") (pinfunction "+VS2_9") (pintype "passive"))
    )
    (net (code "67") (name "GND") (class "Default")
      (node (ref "C147") (pin "1") (pinfunction "1_1") (pintype "passive"))
      (node (ref "C149") (pin "1") (pinfunction "1_1") (pintype "passive"))
      (node (ref "C151") (pin "1") (pinfunction "1_1") (pintype "passive"))
      (node (ref "C152") (pin "1") (pinfunction "1_1") (pintype "passive"))
      (node (ref "C153") (pin "1") (pinfunction "1_1") (pintype "passive"))
      (node (ref "C156") (pin "1") (pinfunction "1_1") (pintype "passive"))
      (node (ref "C157") (pin "1") (pinfunction "1_1") (pintype "passive"))
      (node (ref "C158") (pin "1") (pinfunction "1_1") (pintype "passive"))
      (node (ref "C161") (pin "1") (pinfunction "1_1") (pintype "passive"))
      (node (ref "C162") (pin "1") (pinfunction "1_1") (pintype "passive"))
      (node (ref "C164") (pin "1") (pinfunction "1_1") (pintype "passive"))
      (node (ref "C165") (pin "1") (pinfunction "1_1") (pintype "passive"))
      (node (ref "C166") (pin "1") (pinfunction "1_1") (pintype "passive"))
      (node (ref "C167") (pin "1") (pinfunction "1_1") (pintype "passive"))
      (node (ref "C170") (pin "1") (pinfunction "1_1") (pintype "passive"))
      (node (ref "C171") (pin "1") (pinfunction "1_1") (pintype "passive"))
      (node (ref "C172") (pin "1") (pinfunction "1_1") (pintype "passive"))
      (node (ref "C173") (pin "1") (pinfunction "1_1") (pintype "passive"))
      (node (ref "C174") (pin "1") (pinfunction "1_1") (pintype "passive"))
      (node (ref "C175") (pin "1") (pinfunction "1_1") (pintype "passive"))
      (node (ref "C176") (pin "1") (pinfunction "1_1") (pintype "passive"))
      (node (ref "C177") (pin "1") (pinfunction "1_1") (pintype "passive"))
      (node (ref "C178") (pin "1") (pinfunction "1_1") (pintype "passive"))
      (node (ref "C179") (pin "1") (pinfunction "1_1") (pintype "passive"))
      (node (ref "C182") (pin "1") (pinfunction "1_1") (pintype "passive"))
      (node (ref "C183") (pin "1") (pinfunction "1_1") (pintype "passive"))
      (node (ref "C184") (pin "1") (pinfunction "1_1") (pintype "passive"))
      (node (ref "C186") (pin "1") (pinfunction "1_1") (pintype "passive"))
      (node (ref "C187") (pin "1") (pinfunction "1_1") (pintype "passive"))
      (node (ref "C188") (pin "1") (pinfunction "1_1") (pintype "passive"))
      (node (ref "C189") (pin "1") (pinfunction "1_1") (pintype "passive"))
      (node (ref "C190") (pin "1") (pinfunction "1_1") (pintype "passive"))
      (node (ref "J6") (pin "2") (pinfunction "2_2") (pintype "passive"))
      (node (ref "J6") (pin "3") (pinfunction "3_3") (pintype "passive"))
      (node (ref "J6") (pin "4") (pinfunction "4_4") (pintype "passive"))
      (node (ref "J6") (pin "5") (pinfunction "5_5") (pintype "passive"))
      (node (ref "J7") (pin "2") (pinfunction "2_2") (pintype "passive"))
      (node (ref "J7") (pin "3") (pinfunction "3_3") (pintype "passive"))
      (node (ref "J7") (pin "4") (pinfunction "4_4") (pintype "passive"))
      (node (ref "J7") (pin "5") (pinfunction "5_5") (pintype "passive"))
      (node (ref "R101") (pin "2") (pinfunction "2_2") (pintype "passive"))
      (node (ref "R105") (pin "1") (pinfunction "1_1") (pintype "passive"))
      (node (ref "R109") (pin "2") (pinfunction "2_2") (pintype "passive"))
      (node (ref "R110") (pin "1") (pinfunction "1_1") (pintype "passive"))
      (node (ref "R111") (pin "1") (pinfunction "1_1") (pintype "passive"))
      (node (ref "R97") (pin "1") (pinfunction "1_1") (pintype "passive"))
      (node (ref "TP12") (pin "1") (pinfunction "1_1") (pintype "passive"))
      (node (ref "U8") (pin "17") (pinfunction "AGND_17") (pintype "passive"))
      (node (ref "U8") (pin "18") (pinfunction "AGND_18") (pintype "passive"))
      (node (ref "U8") (pin "21") (pinfunction "AGND_21") (pintype "passive"))
      (node (ref "U8") (pin "24") (pinfunction "AGND_24") (pintype "passive"))
      (node (ref "U8") (pin "27") (pinfunction "AGND_27") (pintype "passive"))
      (node (ref "U8") (pin "28") (pinfunction "AGND_28") (pintype "passive"))
      (node (ref "U8") (pin "31") (pinfunction "AGND_31") (pintype "passive"))
      (node (ref "U8") (pin "32") (pinfunction "AGND_32") (pintype "passive"))
      (node (ref "U8") (pin "39") (pinfunction "DRGND_39") (pintype "passive"))
      (node (ref "U8") (pin "49") (pinfunction "DRGND_49") (pintype "passive"))
      (node (ref "U8") (pin "59") (pinfunction "DRGND_59") (pintype "passive"))
      (node (ref "U8") (pin "PAD") (pinfunction "DRGND_PAD") (pintype "passive"))
    )
    (net (code "68") (name "Net-(R101-Pad1)") (class "Default")
      (node (ref "R101") (pin "1") (pinfunction "1_1") (pintype "passive"))
      (node (ref "R98") (pin "2") (pinfunction "2_2") (pintype "passive"))
    )
    (net (code "69") (name "Net-(R106-Pad2)") (class "Default")
      (node (ref "R106") (pin "2") (pinfunction "2_2") (pintype "passive"))
      (node (ref "R109") (pin "1") (pinfunction "1_1") (pintype "passive"))
    )
    (net (code "70") (name "Net-(U9A-+FB1)") (class "Default")
      (node (ref "R100") (pin "1") (pinfunction "1_1") (pintype "passive"))
      (node (ref "U9") (pin "2") (pinfunction "+FB1_2") (pintype "passive"))
    )
    (net (code "71") (name "Net-(U9A-+IN1)") (class "Default")
      (node (ref "R94") (pin "2") (pinfunction "2_2") (pintype "passive"))
      (node (ref "R95") (pin "1") (pinfunction "1_1") (pintype "passive"))
      (node (ref "U9") (pin "24") (pinfunction "+IN1_24") (pintype "passive"))
    )
    (net (code "72") (name "Net-(U9A--FB1)") (class "Default")
      (node (ref "R94") (pin "1") (pinfunction "1_1") (pintype "passive"))
      (node (ref "U9") (pin "23") (pinfunction "-FB1_23") (pintype "passive"))
    )
    (net (code "73") (name "Net-(U9A--IN1)") (class "Default")
      (node (ref "R100") (pin "2") (pinfunction "2_2") (pintype "passive"))
      (node (ref "R98") (pin "1") (pinfunction "1_1") (pintype "passive"))
      (node (ref "U9") (pin "1") (pinfunction "-IN1_1") (pintype "passive"))
    )
    (net (code "74") (name "Net-(U9B-+FB2)") (class "Default")
      (node (ref "R108") (pin "1") (pinfunction "1_1") (pintype "passive"))
      (node (ref "U9") (pin "8") (pinfunction "+FB2_8") (pintype "passive"))
    )
    (net (code "75") (name "Net-(U9B-+IN2)") (class "Default")
      (node (ref "R102") (pin "2") (pinfunction "2_2") (pintype "passive"))
      (node (ref "R103") (pin "1") (pinfunction "1_1") (pintype "passive"))
      (node (ref "U9") (pin "6") (pinfunction "+IN2_6") (pintype "passive"))
    )
    (net (code "76") (name "Net-(U9B--FB2)") (class "Default")
      (node (ref "R102") (pin "1") (pinfunction "1_1") (pintype "passive"))
      (node (ref "U9") (pin "5") (pinfunction "-FB2_5") (pintype "passive"))
    )
    (net (code "77") (name "Net-(U9B--IN2)") (class "Default")
      (node (ref "R106") (pin "1") (pinfunction "1_1") (pintype "passive"))
      (node (ref "R108") (pin "2") (pinfunction "2_2") (pintype "passive"))
      (node (ref "U9") (pin "7") (pinfunction "-IN2_7") (pintype "passive"))
    )
    (net (code "78") (name "VCM") (class "Default")
      (node (ref "C147") (pin "2") (pinfunction "2_2") (pintype "passive"))
      (node (ref "C149") (pin "2") (pinfunction "2_2") (pintype "passive"))
      (node (ref "U8") (pin "23") (pinfunction "CM_23") (pintype "passive"))
      (node (ref "U9") (pin "11") (pinfunction "VOCM2_11") (pintype "passive"))
      (node (ref "U9") (pin "17") (pinfunction "VOCM1_17") (pintype "passive"))
    )
    (net (code "79") (name "unconnected-(U8C-NC-Pad22)") (class "Default")
      (node (ref "U8") (pin "22") (pinfunction "NC_22") (pintype "passive+no_connect"))
    )
  )
)
